# mcu.net
KiCad netlist of a schematic drawn in Altium Designer
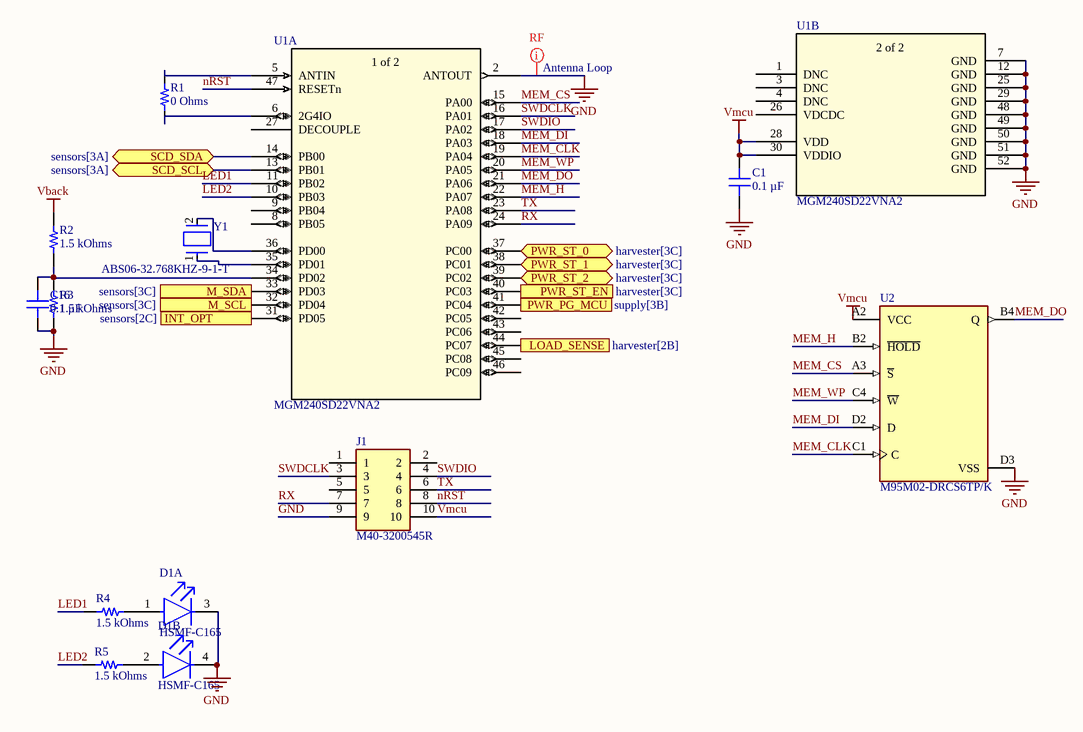
[diagram p0: mcu.SchDoc]

(export (version "E")
  (design (tool "Eeschema 10.0.6"))
  (components
    (comp (ref "C1")
      (value "0.1 µF")
      (footprint "CAP 0402_1005")
      (description "CAP CER 0.1UF 4V X5R 0402")
      (fields (field (name "PART NUMBER") "C0402C104K7PAC7867") (field (name "MANUFACTURER") "KEMET"))
      (libsource (lib "Celestial Altium Library - altium_library") (part "Capacitor"))
    )
    (comp (ref "C16")
      (value "0.1 µF")
      (footprint "CAP 0402_1005")
      (description "CAP CER 0.1UF 4V X5R 0402")
      (fields (field (name "PART NUMBER") "C0402C104K7PAC7867") (field (name "MANUFACTURER") "KEMET"))
      (libsource (lib "Celestial Altium Library - altium_library") (part "Capacitor"))
    )
    (comp (ref "D1")
      (value "HSMF-C165")
      (footprint "FP-HSMF-C165-MFG")
      (description "LED GREEN/RED DIFFUSED 0603 SMD")
      (libsource (lib "Altium Content Vault") (part "7c1fe340d8ce6b5db8c50b7ec3493de"))
    )
    (comp (ref "J1")
      (value "M40-3200545R")
      (footprint "HARWIN_M40-3200545R")
      (description "Connector Header Surface Mount 10 position 0.039 _1.00mm_")
      (fields (field (name "MF") "Harwin Inc."))
      (libsource (lib "M40-3200545R") (part "M40-3200545R"))
    )
    (comp (ref "R1")
      (value "0 Ohms")
      (footprint "RES 0201_0603")
      (description "RES SMD 10 OHM 1% 1/20W 0201")
      (fields
        (field (name "PART NUMBER") "CRG0201F10R")
        (field (name "MANUFACTURER") "TE Connectivity Passive Product")
      )
      (libsource (lib "Celestial Altium Library - altium_library") (part "Resistor"))
    )
    (comp (ref "R2")
      (value "1.5 kOhms")
      (footprint "RES 0402_1005")
      (description "RES 1.5K OHM 0.05% 1/10W 0402")
      (fields
        (field (name "PART NUMBER") "ERA-2VRW1501X")
        (field (name "MANUFACTURER") "Panasonic Electronic Components")
      )
      (libsource (lib "Celestial Altium Library - altium_library") (part "Resistor"))
    )
    (comp (ref "R3")
      (value "1.5 kOhms")
      (footprint "RES 0402_1005")
      (description "RES 1.5K OHM 0.05% 1/10W 0402")
      (fields
        (field (name "PART NUMBER") "ERA-2VRW1501X")
        (field (name "MANUFACTURER") "Panasonic Electronic Components")
      )
      (libsource (lib "Celestial Altium Library - altium_library") (part "Resistor"))
    )
    (comp (ref "R4")
      (value "1.5 kOhms")
      (footprint "RES 0402_1005")
      (description "RES 1.5K OHM 0.05% 1/10W 0402")
      (fields
        (field (name "PART NUMBER") "ERA-2VRW1501X")
        (field (name "MANUFACTURER") "Panasonic Electronic Components")
      )
      (libsource (lib "Celestial Altium Library - altium_library") (part "Resistor"))
    )
    (comp (ref "R5")
      (value "1.5 kOhms")
      (footprint "RES 0402_1005")
      (description "RES 1.5K OHM 0.05% 1/10W 0402")
      (fields
        (field (name "PART NUMBER") "ERA-2VRW1501X")
        (field (name "MANUFACTURER") "Panasonic Electronic Components")
      )
      (libsource (lib "Celestial Altium Library - altium_library") (part "Resistor"))
    )
    (comp (ref "U1")
      (value "MGM240SD22VNA2")
      (footprint "xGM240S")
      (description "No Description Available")
      (libsource (lib "MGM240SD22VNA2") (part "MGM240SD22VNA2"))
    )
    (comp (ref "U2")
      (value "M95M02-DRCS6TP/K")
      (footprint "FP-WLCSP8-E1c_WLCSP8_noBS-MFG")
      (description "IC EEPROM 2M SPI 5MHZ 8WLCSP")
      (fields
        (field (name "MANUFACTURER") "STMicroelectronics")
        (field (name "OCTOPART") "https://octopart.com/m95m02-drcs6tp%2Fk-stmicroelectronics-30038214")
      )
      (libsource (lib "Altium Content Vault") (part "bea03319f7f001eda663444d77e1042"))
    )
    (comp (ref "Y1")
      (value "ABS06-32.768KHZ-9-1-T")
      (footprint "FP-ABS06-MFG")
      (description "Crystal 32.768kHz ±10ppm (Tol) 9pF FUND 90kΩ 2-Pin Mini-CSMD T/R")
      (fields (field (name "TOLERANCE") "10ppm"))
      (libsource (lib "Altium Content Vault") (part "c23a69dc6c9e2f18f2079038eb95dd1"))
    )
  )
  (nets
    (net (code "1") (name "/INT_OPT") (class "Default")
      (node (ref "U1") (pin "31") (pinfunction "PD05_31") (pintype "bidirectional"))
    )
    (net (code "2") (name "/LED1") (class "Default")
      (node (ref "R4") (pin "2") (pinfunction "2_2") (pintype "passive"))
      (node (ref "U1") (pin "11") (pinfunction "PB02_11") (pintype "bidirectional"))
    )
    (net (code "3") (name "/LED2") (class "Default")
      (node (ref "R5") (pin "2") (pinfunction "2_2") (pintype "passive"))
      (node (ref "U1") (pin "10") (pinfunction "PB03_10") (pintype "bidirectional"))
    )
    (net (code "4") (name "/LOAD_SENSE") (class "Default")
      (node (ref "U1") (pin "44") (pinfunction "PC07_44") (pintype "bidirectional"))
    )
    (net (code "5") (name "/MEM_CLK") (class "Default")
      (node (ref "U1") (pin "19") (pinfunction "PA04_19") (pintype "bidirectional"))
      (node (ref "U2") (pin "C1") (pinfunction "C_C1") (pintype "input"))
    )
    (net (code "6") (name "/MEM_CS") (class "Default")
      (node (ref "U1") (pin "15") (pinfunction "PA00_15") (pintype "bidirectional"))
      (node (ref "U2") (pin "A3") (pinfunction "~{S}_A3") (pintype "input"))
    )
    (net (code "7") (name "/MEM_DI") (class "Default")
      (node (ref "U1") (pin "18") (pinfunction "PA03_18") (pintype "bidirectional"))
      (node (ref "U2") (pin "D2") (pinfunction "D_D2") (pintype "input"))
    )
    (net (code "8") (name "/MEM_DO") (class "Default")
      (node (ref "U1") (pin "21") (pinfunction "PA06_21") (pintype "bidirectional"))
      (node (ref "U2") (pin "B4") (pinfunction "Q_B4") (pintype "output"))
    )
    (net (code "9") (name "/MEM_H") (class "Default")
      (node (ref "U1") (pin "22") (pinfunction "PA07_22") (pintype "bidirectional"))
      (node (ref "U2") (pin "B2") (pinfunction "~{HOLD}_B2") (pintype "input"))
    )
    (net (code "10") (name "/MEM_WP") (class "Default")
      (node (ref "U1") (pin "20") (pinfunction "PA05_20") (pintype "bidirectional"))
      (node (ref "U2") (pin "C4") (pinfunction "~{W}_C4") (pintype "input"))
    )
    (net (code "11") (name "/M_SCL") (class "Default")
      (node (ref "U1") (pin "32") (pinfunction "PD04_32") (pintype "bidirectional"))
    )
    (net (code "12") (name "/M_SDA") (class "Default")
      (node (ref "U1") (pin "33") (pinfunction "PD03_33") (pintype "bidirectional"))
    )
    (net (code "13") (name "/PWR_PG_MCU") (class "Default")
      (node (ref "U1") (pin "41") (pinfunction "PC04_41") (pintype "bidirectional"))
    )
    (net (code "14") (name "/PWR_ST_0") (class "Default")
      (node (ref "U1") (pin "37") (pinfunction "PC00_37") (pintype "bidirectional"))
    )
    (net (code "15") (name "/PWR_ST_1") (class "Default")
      (node (ref "U1") (pin "38") (pinfunction "PC01_38") (pintype "bidirectional"))
    )
    (net (code "16") (name "/PWR_ST_2") (class "Default")
      (node (ref "U1") (pin "39") (pinfunction "PC02_39") (pintype "bidirectional"))
    )
    (net (code "17") (name "/PWR_ST_EN") (class "Default")
      (node (ref "U1") (pin "40") (pinfunction "PC03_40") (pintype "bidirectional"))
    )
    (net (code "18") (name "/RX") (class "Default")
      (node (ref "J1") (pin "7") (pinfunction "7_7") (pintype "passive"))
      (node (ref "U1") (pin "24") (pinfunction "PA09_24") (pintype "bidirectional"))
    )
    (net (code "19") (name "/SCD_SCL") (class "Default")
      (node (ref "U1") (pin "13") (pinfunction "PB01_13") (pintype "bidirectional"))
    )
    (net (code "20") (name "/SCD_SDA") (class "Default")
      (node (ref "U1") (pin "14") (pinfunction "PB00_14") (pintype "bidirectional"))
    )
    (net (code "21") (name "/SWDCLK") (class "Default")
      (node (ref "J1") (pin "3") (pinfunction "3_3") (pintype "passive"))
      (node (ref "U1") (pin "16") (pinfunction "PA01_16") (pintype "bidirectional"))
    )
    (net (code "22") (name "/SWDIO") (class "Default")
      (node (ref "J1") (pin "4") (pinfunction "4_4") (pintype "passive"))
      (node (ref "U1") (pin "17") (pinfunction "PA02_17") (pintype "bidirectional"))
    )
    (net (code "23") (name "/TX") (class "Default")
      (node (ref "J1") (pin "6") (pinfunction "6_6") (pintype "passive"))
      (node (ref "U1") (pin "23") (pinfunction "PA08_23") (pintype "bidirectional"))
    )
    (net (code "24") (name "/nRST") (class "Default")
      (node (ref "J1") (pin "8") (pinfunction "8_8") (pintype "passive"))
      (node (ref "U1") (pin "47") (pinfunction "RESETn_47") (pintype "input"))
    )
    (net (code "25") (name "GND") (class "Default")
      (node (ref "C1") (pin "1") (pinfunction "1_1") (pintype "passive"))
      (node (ref "C16") (pin "1") (pinfunction "1_1") (pintype "passive"))
      (node (ref "D1") (pin "3") (pinfunction "GREEN_C_3") (pintype "passive"))
      (node (ref "D1") (pin "4") (pinfunction "RED_C_4") (pintype "passive"))
      (node (ref "J1") (pin "9") (pinfunction "9_9") (pintype "passive"))
      (node (ref "R3") (pin "2") (pinfunction "2_2") (pintype "passive"))
      (node (ref "U1") (pin "12") (pinfunction "GND_12") (pintype "power_in"))
      (node (ref "U1") (pin "2") (pinfunction "ANTOUT_2") (pintype "output"))
      (node (ref "U1") (pin "25") (pinfunction "GND_25") (pintype "power_in"))
      (node (ref "U1") (pin "29") (pinfunction "GND_29") (pintype "power_in"))
      (node (ref "U1") (pin "48") (pinfunction "GND_48") (pintype "power_in"))
      (node (ref "U1") (pin "49") (pinfunction "GND_49") (pintype "power_in"))
      (node (ref "U1") (pin "50") (pinfunction "GND_50") (pintype "power_in"))
      (node (ref "U1") (pin "51") (pinfunction "GND_51") (pintype "power_in"))
      (node (ref "U1") (pin "52") (pinfunction "GND_52") (pintype "power_in"))
      (node (ref "U1") (pin "7") (pinfunction "GND_7") (pintype "power_in"))
      (node (ref "U2") (pin "D3") (pinfunction "VSS_D3") (pintype "power_in"))
    )
    (net (code "26") (name "Net-(D1A-GREEN_A)") (class "Default")
      (node (ref "D1") (pin "1") (pinfunction "GREEN_A_1") (pintype "passive"))
      (node (ref "R4") (pin "1") (pinfunction "1_1") (pintype "passive"))
    )
    (net (code "27") (name "Net-(D1B-RED_A)") (class "Default")
      (node (ref "D1") (pin "2") (pinfunction "RED_A_2") (pintype "passive"))
      (node (ref "R5") (pin "1") (pinfunction "1_1") (pintype "passive"))
    )
    (net (code "28") (name "Net-(U1A-2G4IO)") (class "Default")
      (node (ref "R1") (pin "1") (pinfunction "1_1") (pintype "passive"))
      (node (ref "U1") (pin "6") (pinfunction "2G4IO_6") (pintype "bidirectional"))
    )
    (net (code "29") (name "Net-(U1A-ANTIN)") (class "Default")
      (node (ref "R1") (pin "2") (pinfunction "2_2") (pintype "passive"))
      (node (ref "U1") (pin "5") (pinfunction "ANTIN_5") (pintype "input"))
    )
    (net (code "30") (name "Net-(U1A-PD00)") (class "Default")
      (node (ref "U1") (pin "36") (pinfunction "PD00_36") (pintype "bidirectional"))
      (node (ref "Y1") (pin "2") (pinfunction "2_2") (pintype "passive"))
    )
    (net (code "31") (name "Net-(U1A-PD01)") (class "Default")
      (node (ref "U1") (pin "35") (pinfunction "PD01_35") (pintype "bidirectional"))
      (node (ref "Y1") (pin "1") (pinfunction "1_1") (pintype "passive"))
    )
    (net (code "32") (name "Net-(U1A-PD02)") (class "Default")
      (node (ref "C16") (pin "2") (pinfunction "2_2") (pintype "passive"))
      (node (ref "R2") (pin "2") (pinfunction "2_2") (pintype "passive"))
      (node (ref "R3") (pin "1") (pinfunction "1_1") (pintype "passive"))
      (node (ref "U1") (pin "34") (pinfunction "PD02_34") (pintype "bidirectional"))
    )
    (net (code "33") (name "Vback") (class "Default")
      (node (ref "R2") (pin "1") (pinfunction "1_1") (pintype "passive"))
    )
    (net (code "34") (name "Vmcu") (class "Default")
      (node (ref "C1") (pin "2") (pinfunction "2_2") (pintype "passive"))
      (node (ref "J1") (pin "10") (pinfunction "10_10") (pintype "passive"))
      (node (ref "U1") (pin "28") (pinfunction "VDD_28") (pintype "power_in"))
      (node (ref "U1") (pin "30") (pinfunction "VDDIO_30") (pintype "power_in"))
      (node (ref "U2") (pin "A2") (pinfunction "VCC_A2") (pintype "power_in"))
    )
    (net (code "35") (name "unconnected-(J1-Pad1)") (class "Default")
      (node (ref "J1") (pin "1") (pinfunction "1_1") (pintype "passive"))
    )
    (net (code "36") (name "unconnected-(J1-Pad2)") (class "Default")
      (node (ref "J1") (pin "2") (pinfunction "2_2") (pintype "passive"))
    )
    (net (code "37") (name "unconnected-(J1-Pad5)") (class "Default")
      (node (ref "J1") (pin "5") (pinfunction "5_5") (pintype "passive"))
    )
    (net (code "38") (name "unconnected-(U1A-DECOUPLE-Pad27)") (class "Default")
      (node (ref "U1") (pin "27") (pinfunction "DECOUPLE_27") (pintype "passive"))
    )
    (net (code "39") (name "unconnected-(U1A-PB04-Pad9)") (class "Default")
      (node (ref "U1") (pin "9") (pinfunction "PB04_9") (pintype "bidirectional"))
    )
    (net (code "40") (name "unconnected-(U1A-PB05-Pad8)") (class "Default")
      (node (ref "U1") (pin "8") (pinfunction "PB05_8") (pintype "bidirectional"))
    )
    (net (code "41") (name "unconnected-(U1A-PC05-Pad42)") (class "Default")
      (node (ref "U1") (pin "42") (pinfunction "PC05_42") (pintype "bidirectional"))
    )
    (net (code "42") (name "unconnected-(U1A-PC06-Pad43)") (class "Default")
      (node (ref "U1") (pin "43") (pinfunction "PC06_43") (pintype "bidirectional"))
    )
    (net (code "43") (name "unconnected-(U1A-PC08-Pad45)") (class "Default")
      (node (ref "U1") (pin "45") (pinfunction "PC08_45") (pintype "bidirectional"))
    )
    (net (code "44") (name "unconnected-(U1A-PC09-Pad46)") (class "Default")
      (node (ref "U1") (pin "46") (pinfunction "PC09_46") (pintype "bidirectional"))
    )
    (net (code "45") (name "unconnected-(U1B-DNC-Pad1)") (class "Default")
      (node (ref "U1") (pin "1") (pinfunction "DNC_1") (pintype "passive"))
    )
    (net (code "46") (name "unconnected-(U1B-DNC-Pad3)") (class "Default")
      (node (ref "U1") (pin "3") (pinfunction "DNC_3") (pintype "passive"))
    )
    (net (code "47") (name "unconnected-(U1B-DNC-Pad4)") (class "Default")
      (node (ref "U1") (pin "4") (pinfunction "DNC_4") (pintype "passive"))
    )
    (net (code "48") (name "unconnected-(U1B-VDCDC-Pad26)") (class "Default")
      (node (ref "U1") (pin "26") (pinfunction "VDCDC_26") (pintype "power_in"))
    )
  )
)
